# DB10005_Wireless.net
KiCad netlist of a schematic drawn in Altium Designer
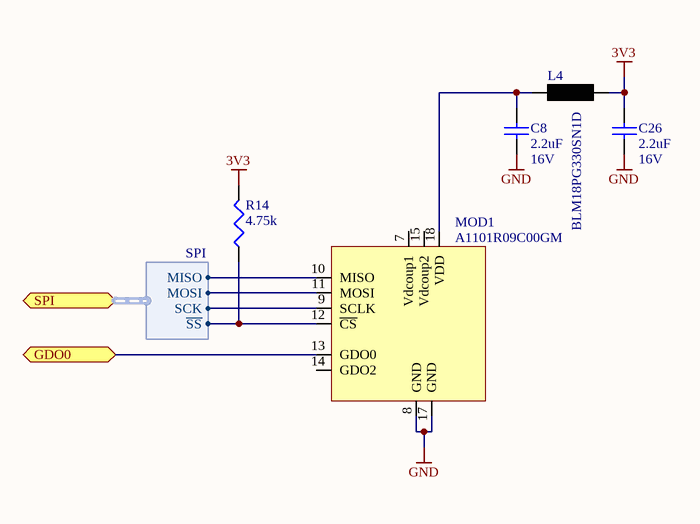
[diagram p0: DB10005_Wireless.SchDoc]

(export (version "E")
  (design (tool "Eeschema 10.0.6"))
  (components
    (comp (ref "C8")
      (value "2.2uF")
      (footprint "C0603")
      (description "Capacitor, 2.2uF, 16V, X5R")
      (fields (field (name "VOLTAGE RATING") "16V"))
      (libsource (lib "AR_Capacitors_Ceramic") (part "2.2uF/0603/CER/16V"))
    )
    (comp (ref "C26")
      (value "2.2uF")
      (footprint "C0603")
      (description "Capacitor, 2.2uF, 16V, X5R")
      (fields (field (name "VOLTAGE RATING") "16V"))
      (libsource (lib "AR_Capacitors_Ceramic") (part "2.2uF/0603/CER/16V"))
    )
    (comp (ref "L4")
      (value "BLM18PG330SN1D")
      (footprint "L0603")
      (description "Ferrite Bead, Impedance:33ohm, DC Resistance Max:0.025ohm, DC Current Rating:3A")
      (libsource (lib "AR_Inductors") (part "BLM18PG330SN1D"))
    )
    (comp (ref "MOD1")
      (value "A1101R09C00GM")
      (footprint "AxxLR09_Short")
      (description "SubRF tranceiver module")
      (libsource (lib "AR_Modules") (part "A1101R09C00GM"))
    )
    (comp (ref "R14")
      (value "4.75k")
      (footprint "0402")
      (description "Resistor, 4.75k, 0.1%, 0.0625W, 50V, 100PPM, 0402")
      (libsource (lib "AR_Resistors_SMD") (part "4.75k/0402/0063W/50V"))
    )
  )
  (nets
    (net (code "2") (name "/GDO0") (class "Default")
      (node (ref "MOD1") (pin "13") (pinfunction "GDO0_13") (pintype "passive"))
    )
    (net (code "3") (name "/MISO") (class "Default")
      (node (ref "MOD1") (pin "10") (pinfunction "MISO_10") (pintype "passive"))
    )
    (net (code "4") (name "/MOSI") (class "Default")
      (node (ref "MOD1") (pin "11") (pinfunction "MOSI_11") (pintype "passive"))
    )
    (net (code "5") (name "/SCK") (class "Default")
      (node (ref "MOD1") (pin "9") (pinfunction "SCLK_9") (pintype "passive"))
    )
    (net (code "7") (name "/~{SS}") (class "Default")
      (node (ref "MOD1") (pin "12") (pinfunction "~{CS}_12") (pintype "passive"))
      (node (ref "R14") (pin "1") (pinfunction "1_1") (pintype "passive"))
    )
    (net (code "8") (name "3V3") (class "Default")
      (node (ref "C26") (pin "2") (pinfunction "2_2") (pintype "passive"))
      (node (ref "L4") (pin "2") (pinfunction "2_2") (pintype "passive"))
      (node (ref "R14") (pin "2") (pinfunction "2_2") (pintype "passive"))
    )
    (net (code "9") (name "GND") (class "Default")
      (node (ref "C26") (pin "1") (pinfunction "1_1") (pintype "passive"))
      (node (ref "C8") (pin "1") (pinfunction "1_1") (pintype "passive"))
      (node (ref "MOD1") (pin "17") (pinfunction "GND_17") (pintype "passive"))
      (node (ref "MOD1") (pin "8") (pinfunction "GND_8") (pintype "passive"))
    )
    (net (code "10") (name "Net-(MOD1-VDD)") (class "Default")
      (node (ref "C8") (pin "2") (pinfunction "2_2") (pintype "passive"))
      (node (ref "L4") (pin "1") (pinfunction "1_1") (pintype "passive"))
      (node (ref "MOD1") (pin "18") (pinfunction "VDD_18") (pintype "passive"))
    )
    (net (code "11") (name "unconnected-(MOD1-GDO2-Pad14)") (class "Default")
      (node (ref "MOD1") (pin "14") (pinfunction "GDO2_14") (pintype "passive"))
    )
    (net (code "12") (name "unconnected-(MOD1-Vdcoup1-Pad7)") (class "Default")
      (node (ref "MOD1") (pin "7") (pinfunction "Vdcoup1_7") (pintype "passive"))
    )
    (net (code "13") (name "unconnected-(MOD1-Vdcoup2-Pad15)") (class "Default")
      (node (ref "MOD1") (pin "15") (pinfunction "Vdcoup2_15") (pintype "passive"))
    )
  )
)
